# Executive_230V_B.net
KiCad netlist of a schematic drawn in EAGLE
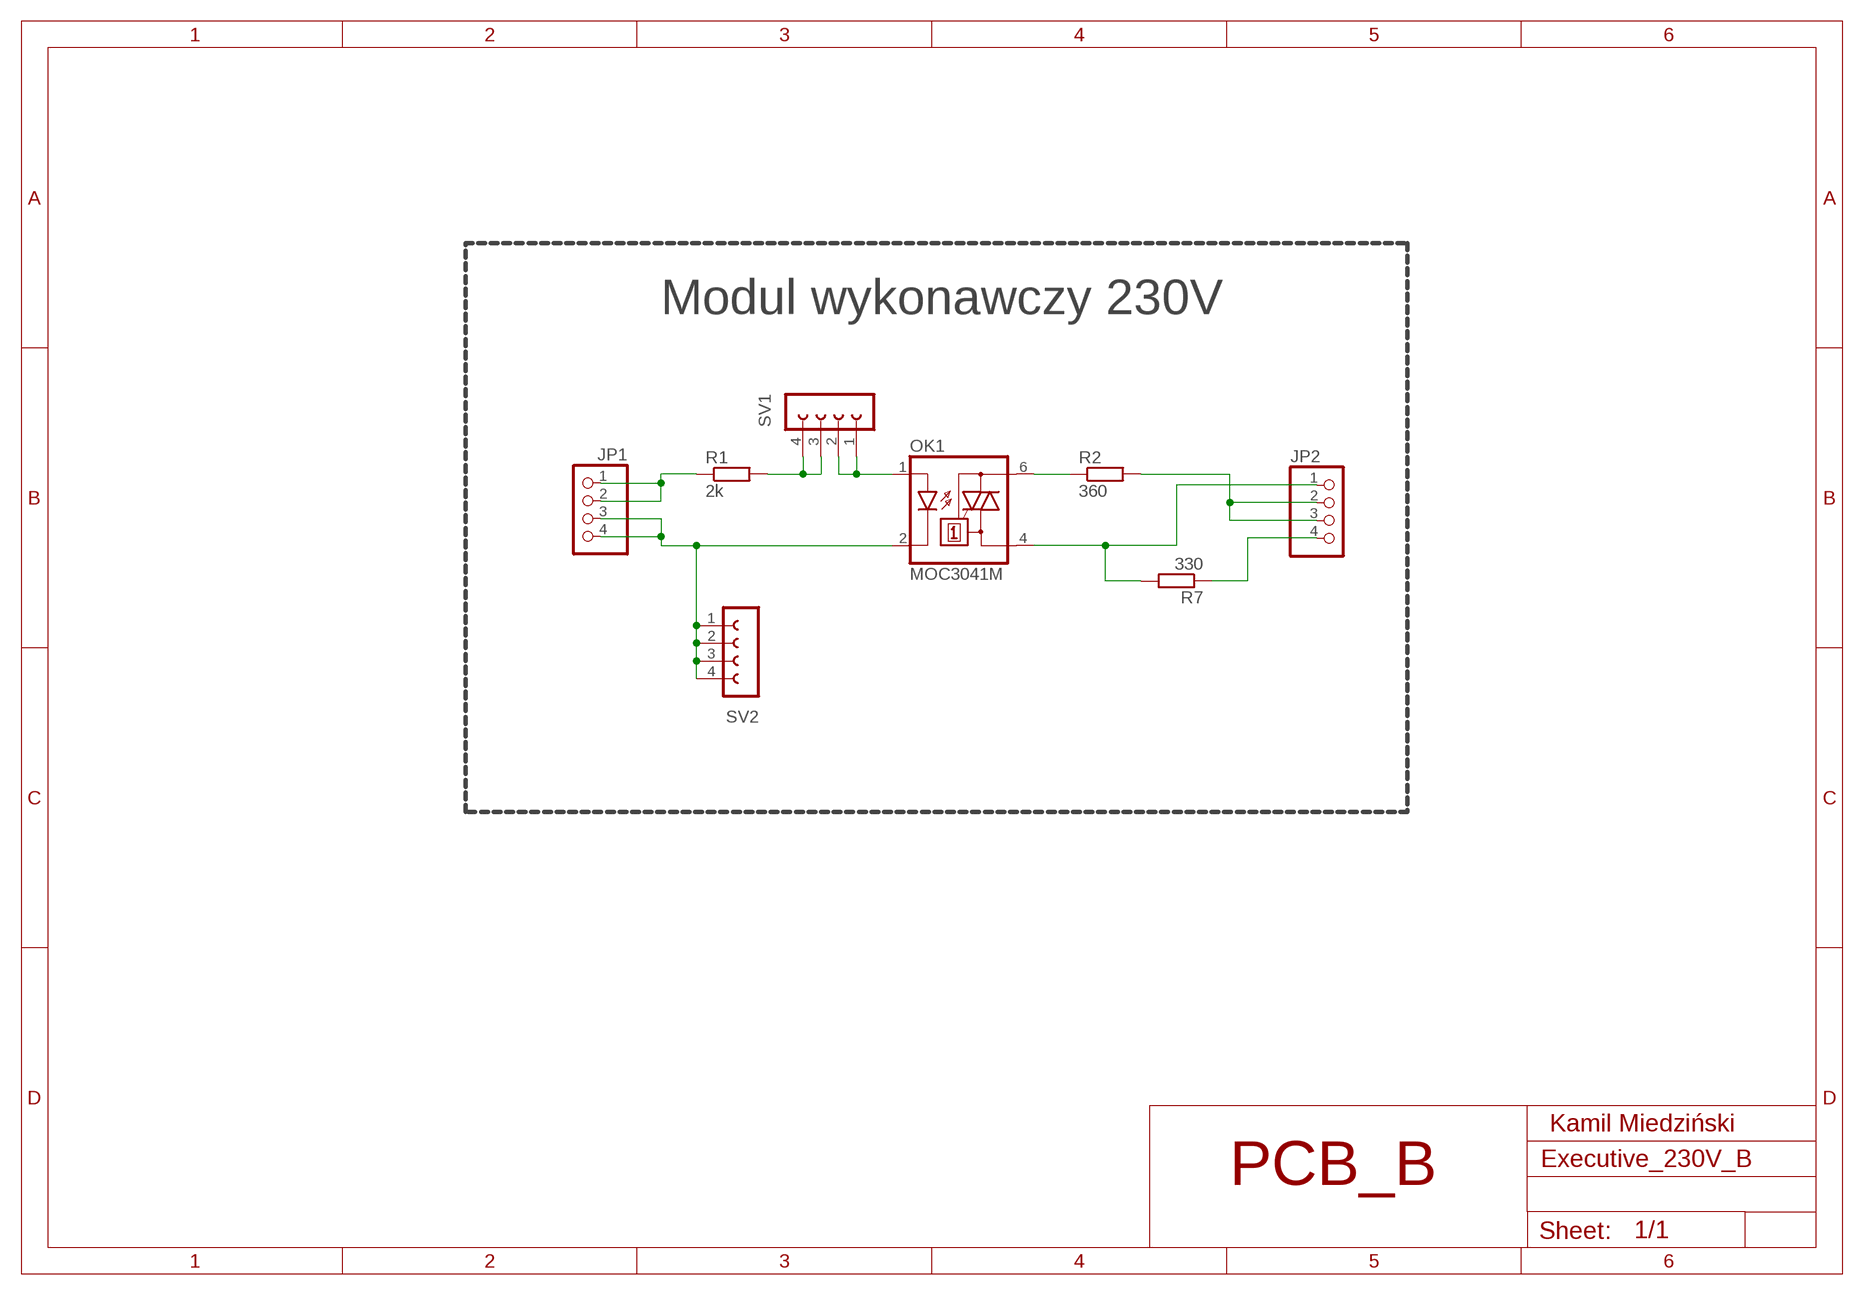
[diagram p0: schematic, sheet 1]

(export (version "E")
  (design (tool "Eeschema 10.0.6"))
  (components
    (comp (ref "JP1")
      (value "PINHD-1X41X04H")
      (footprint "eagle-import:1X04H")
      (libsource (lib "eagle-import") (part "PINHD-1X41X04H"))
    )
    (comp (ref "JP2")
      (value "PINHD-1X41X04H")
      (footprint "eagle-import:1X04H")
      (libsource (lib "eagle-import") (part "PINHD-1X41X04H"))
    )
    (comp (ref "OK1")
      (value "MOC3041M")
      (footprint "eagle-import:DIL06")
      (fields (field (name "MF") "FAIRCHILD SEMICONDUCTOR"))
      (libsource (lib "eagle-import") (part "MOC3041M"))
    )
    (comp (ref "R1")
      (value "2k")
      (footprint "eagle-import:0207_10")
      (libsource (lib "eagle-import") (part "R-EU_0207/10"))
    )
    (comp (ref "R2")
      (value "360")
      (footprint "eagle-import:0207_10")
      (fields (field (name "MF") "TT ELECTRONICS / WELWYN") (field (name "MPN") "MFR4-360RFI"))
      (libsource (lib "eagle-import") (part "R-EU_0207/10"))
    )
    (comp (ref "R7")
      (value "330")
      (footprint "eagle-import:0207_10")
      (libsource (lib "eagle-import") (part "R-EU_0207/10"))
    )
    (comp (ref "SV1")
      (value "FE04-1")
      (footprint "eagle-import:FE04-1")
      (libsource (lib "eagle-import") (part "FE04-1"))
    )
    (comp (ref "SV2")
      (value "FE04-1")
      (footprint "eagle-import:FE04-1")
      (libsource (lib "eagle-import") (part "FE04-1"))
    )
  )
  (nets
    (net (code "1") (name "Net-(JP1-Pad1)") (class "Default")
      (node (ref "JP1") (pin "1") (pinfunction "1_1") (pintype "passive"))
      (node (ref "JP1") (pin "2") (pinfunction "2_2") (pintype "passive"))
      (node (ref "R1") (pin "1") (pinfunction "1_1") (pintype "passive"))
    )
    (net (code "2") (name "Net-(JP2-Pad2)") (class "Default")
      (node (ref "JP2") (pin "2") (pinfunction "2_2") (pintype "passive"))
      (node (ref "JP2") (pin "3") (pinfunction "3_3") (pintype "passive"))
      (node (ref "R2") (pin "2") (pinfunction "2_2") (pintype "passive"))
    )
    (net (code "3") (name "Net-(JP2-Pad4)") (class "Default")
      (node (ref "JP2") (pin "4") (pinfunction "4_4") (pintype "passive"))
      (node (ref "R7") (pin "1") (pinfunction "1_1") (pintype "passive"))
    )
    (net (code "4") (name "Net-(OK1-A)") (class "Default")
      (node (ref "OK1") (pin "1") (pinfunction "A_1") (pintype "passive"))
      (node (ref "SV1") (pin "1") (pinfunction "2_1") (pintype "passive"))
      (node (ref "SV1") (pin "2") (pinfunction "3_2") (pintype "passive"))
    )
    (net (code "5") (name "Net-(OK1-A1)") (class "Default")
      (node (ref "JP2") (pin "1") (pinfunction "1_1") (pintype "passive"))
      (node (ref "OK1") (pin "4") (pinfunction "A1_4") (pintype "passive"))
      (node (ref "R7") (pin "2") (pinfunction "2_2") (pintype "passive"))
    )
    (net (code "6") (name "Net-(OK1-A2)") (class "Default")
      (node (ref "OK1") (pin "6") (pinfunction "A2_6") (pintype "passive"))
      (node (ref "R2") (pin "1") (pinfunction "1_1") (pintype "passive"))
    )
    (net (code "7") (name "Net-(OK1-C)") (class "Default")
      (node (ref "JP1") (pin "3") (pinfunction "3_3") (pintype "passive"))
      (node (ref "JP1") (pin "4") (pinfunction "4_4") (pintype "passive"))
      (node (ref "OK1") (pin "2") (pinfunction "C_2") (pintype "passive"))
      (node (ref "SV2") (pin "1") (pinfunction "2_1") (pintype "passive"))
      (node (ref "SV2") (pin "2") (pinfunction "3_2") (pintype "passive"))
      (node (ref "SV2") (pin "3") (pinfunction "4_3") (pintype "passive"))
      (node (ref "SV2") (pin "4") (pinfunction "5_4") (pintype "passive"))
    )
    (net (code "8") (name "Net-(SV1-4)") (class "Default")
      (node (ref "R1") (pin "2") (pinfunction "2_2") (pintype "passive"))
      (node (ref "SV1") (pin "3") (pinfunction "4_3") (pintype "passive"))
      (node (ref "SV1") (pin "4") (pinfunction "5_4") (pintype "passive"))
    )
  )
)
